# KEYBOARD.net
KiCad netlist of a schematic drawn in Altium Designer
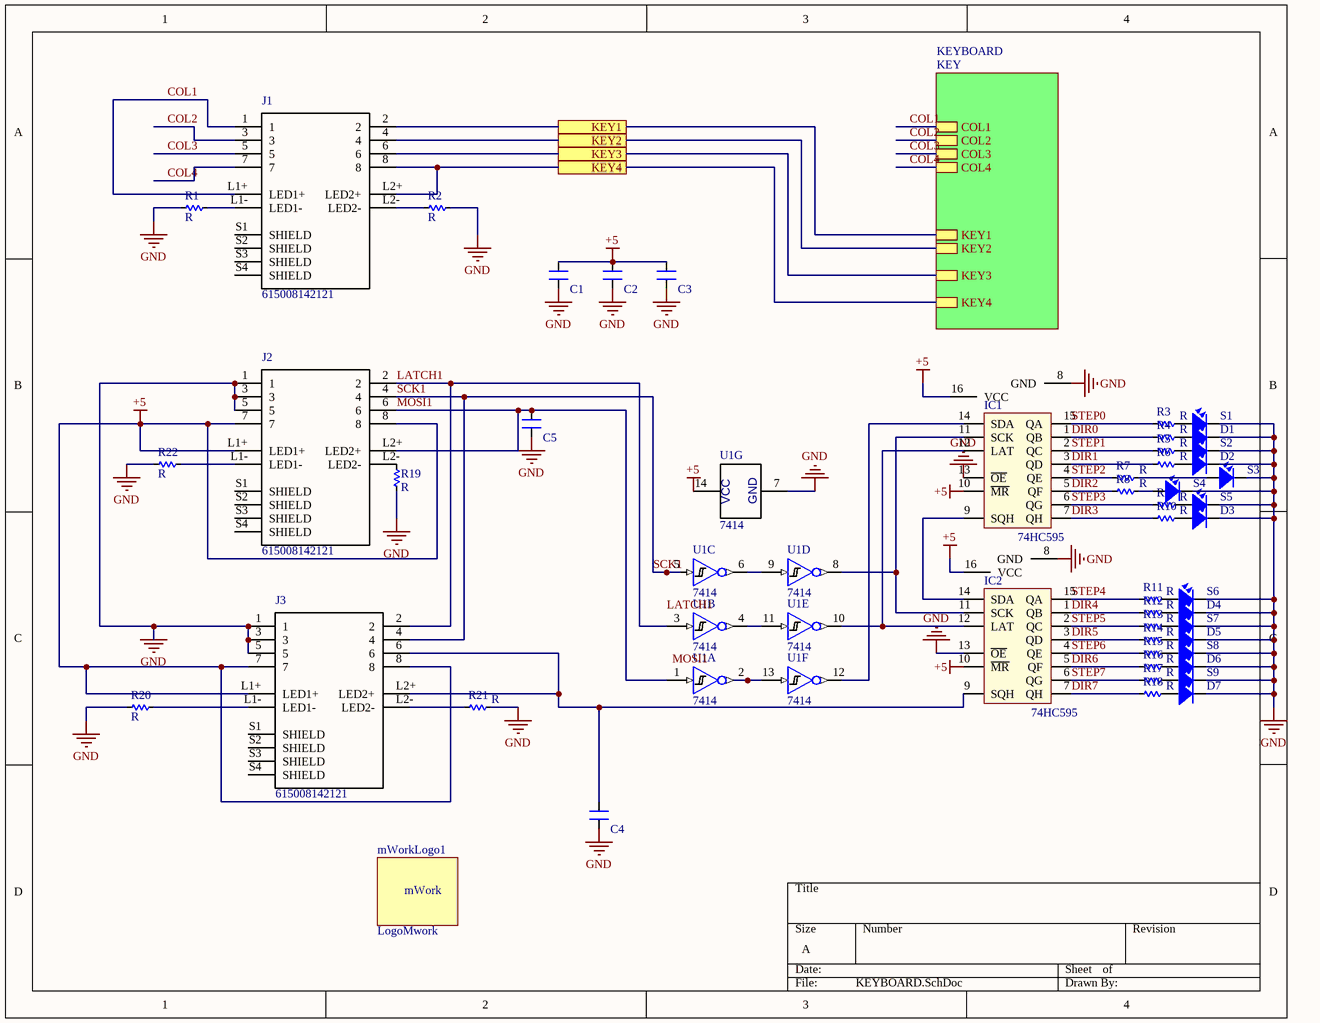
[diagram p0: KEYBOARD.SchDoc]

(export (version "E")
  (design (tool "Eeschema 10.0.6"))
  (components
    (comp (ref "C1") (value "CN") (footprint "CN-SMD-0603_big") (libsource (lib "nhan") (part "CN")))
    (comp (ref "C2") (value "CN") (footprint "CN-SMD-0603_big") (libsource (lib "nhan") (part "CN")))
    (comp (ref "C3") (value "CN") (footprint "CN-SMD-0603_big") (libsource (lib "nhan") (part "CN")))
    (comp (ref "C4") (value "CN") (footprint "CN-SMD-0603_big") (libsource (lib "nhan") (part "CN")))
    (comp (ref "C5") (value "CN") (footprint "CN-SMD-0603_big") (libsource (lib "nhan") (part "CN")))
    (comp (ref "D1") (value "LED") (footprint "LED-0805-Blue") (libsource (lib "LIBRARY") (part "LED SMD")))
    (comp (ref "D2") (value "LED") (footprint "LED-0805-Blue") (libsource (lib "LIBRARY") (part "LED SMD")))
    (comp (ref "D3") (value "LED") (footprint "LED-0805-Blue") (libsource (lib "LIBRARY") (part "LED SMD")))
    (comp (ref "D4") (value "LED") (footprint "LED-0805-Blue") (libsource (lib "LIBRARY") (part "LED SMD")))
    (comp (ref "D5") (value "LED") (footprint "LED-0805-Blue") (libsource (lib "LIBRARY") (part "LED SMD")))
    (comp (ref "D6") (value "LED") (footprint "LED-0805-Blue") (libsource (lib "LIBRARY") (part "LED SMD")))
    (comp (ref "D7") (value "LED") (footprint "LED-0805-Blue") (libsource (lib "LIBRARY") (part "LED SMD")))
    (comp (ref "IC1")
      (value "74HC595")
      (footprint "SO16")
      (description "8 Bit Serial input - Parallel Output")
      (libsource (lib "") (part "74595_1"))
    )
    (comp (ref "IC2")
      (value "74HC595")
      (footprint "SO16")
      (description "8 Bit Serial input - Parallel Output")
      (libsource (lib "BanLinhKien") (part "74595"))
    )
    (comp (ref "J1")
      (value "615008142121")
      (footprint "RJ45_8P8C")
      (description "Conn, Rj45 Jack, Shld, 1port, 8p8c, Cat5")
      (fields (field (name "MF") "WÃ¼rth Elektronik"))
      (libsource (lib "nhan") (part "RJ45_8P8C"))
    )
    (comp (ref "J2")
      (value "615008142121")
      (footprint "RJ45_8P8C")
      (description "Conn, Rj45 Jack, Shld, 1port, 8p8c, Cat5")
      (fields (field (name "MF") "WÃ¼rth Elektronik"))
      (libsource (lib "nhan") (part "RJ45_8P8C"))
    )
    (comp (ref "J3")
      (value "615008142121")
      (footprint "RJ45_8P8C")
      (description "Conn, Rj45 Jack, Shld, 1port, 8p8c, Cat5")
      (fields (field (name "MF") "WÃ¼rth Elektronik"))
      (libsource (lib "nhan") (part "RJ45_8P8C"))
    )
    (comp (ref "mWorkLogo1")
      (value "LogoMwork")
      (footprint "LogoMwork15*6")
      (libsource (lib "nhan") (part "LogoMwork"))
    )
    (comp (ref "R1") (value "R") (footprint "RES-SMD-0603_BIG") (libsource (lib "nhan") (part "R")))
    (comp (ref "R2") (value "R") (footprint "RES-SMD-0603_BIG") (libsource (lib "nhan") (part "R")))
    (comp (ref "R3") (value "R") (footprint "RES-SMD-0603_BIG") (libsource (lib "nhan") (part "R")))
    (comp (ref "R4") (value "R") (footprint "RES-SMD-0603_BIG") (libsource (lib "nhan") (part "R")))
    (comp (ref "R5") (value "R") (footprint "RES-SMD-0603_BIG") (libsource (lib "nhan") (part "R")))
    (comp (ref "R6") (value "R") (footprint "RES-SMD-0603_BIG") (libsource (lib "nhan") (part "R")))
    (comp (ref "R7") (value "R") (footprint "RES-SMD-0603_BIG") (libsource (lib "nhan") (part "R")))
    (comp (ref "R8") (value "R") (footprint "RES-SMD-0603_BIG") (libsource (lib "nhan") (part "R")))
    (comp (ref "R9") (value "R") (footprint "RES-SMD-0603_BIG") (libsource (lib "nhan") (part "R")))
    (comp (ref "R10") (value "R") (footprint "RES-SMD-0603_BIG") (libsource (lib "nhan") (part "R")))
    (comp (ref "R11") (value "R") (footprint "RES-SMD-0603_BIG") (libsource (lib "nhan") (part "R")))
    (comp (ref "R12") (value "R") (footprint "RES-SMD-0603_BIG") (libsource (lib "nhan") (part "R")))
    (comp (ref "R13") (value "R") (footprint "RES-SMD-0603_BIG") (libsource (lib "nhan") (part "R")))
    (comp (ref "R14") (value "R") (footprint "RES-SMD-0603_BIG") (libsource (lib "nhan") (part "R")))
    (comp (ref "R15") (value "R") (footprint "RES-SMD-0603_BIG") (libsource (lib "nhan") (part "R")))
    (comp (ref "R16") (value "R") (footprint "RES-SMD-0603_BIG") (libsource (lib "nhan") (part "R")))
    (comp (ref "R17") (value "R") (footprint "RES-SMD-0603_BIG") (libsource (lib "nhan") (part "R")))
    (comp (ref "R18") (value "R") (footprint "RES-SMD-0603_BIG") (libsource (lib "nhan") (part "R")))
    (comp (ref "R19") (value "R") (footprint "RES-SMD-0603_BIG") (libsource (lib "nhan") (part "R")))
    (comp (ref "R20") (value "R") (footprint "RES-SMD-0603_BIG") (libsource (lib "nhan") (part "R")))
    (comp (ref "R21") (value "R") (footprint "RES-SMD-0603_BIG") (libsource (lib "nhan") (part "R")))
    (comp (ref "R22") (value "R") (footprint "RES-SMD-0603_BIG") (libsource (lib "nhan") (part "R")))
    (comp (ref "S1") (value "LED") (footprint "LED-0805-Blue") (libsource (lib "LIBRARY") (part "LED SMD")))
    (comp (ref "S2") (value "LED") (footprint "LED-0805-Blue") (libsource (lib "LIBRARY") (part "LED SMD")))
    (comp (ref "S3") (value "LED") (footprint "LED-0805-Blue") (libsource (lib "LIBRARY") (part "LED SMD")))
    (comp (ref "S4") (value "LED") (footprint "LED-0805-Blue") (libsource (lib "LIBRARY") (part "LED SMD")))
    (comp (ref "S5") (value "LED") (footprint "LED-0805-Blue") (libsource (lib "LIBRARY") (part "LED SMD")))
    (comp (ref "S6") (value "LED") (footprint "LED-0805-Blue") (libsource (lib "LIBRARY") (part "LED SMD")))
    (comp (ref "S7") (value "LED") (footprint "LED-0805-Blue") (libsource (lib "LIBRARY") (part "LED SMD")))
    (comp (ref "S8") (value "LED") (footprint "LED-0805-Blue") (libsource (lib "LIBRARY") (part "LED SMD")))
    (comp (ref "S9") (value "LED") (footprint "LED-0805-Blue") (libsource (lib "LIBRARY") (part "LED SMD")))
    (comp (ref "U1")
      (value "7414")
      (footprint "SO14")
      (description "IC, M74HC04M, Hex Inverter, SO-14")
      (libsource (lib "BanLinhKien") (part "7414"))
    )
  )
  (nets
    (net (code "1") (name "+5") (class "Default")
      (node (ref "C1") (pin "2") (pinfunction "2_2") (pintype "passive"))
      (node (ref "C2") (pin "2") (pinfunction "2_2") (pintype "passive"))
      (node (ref "C3") (pin "2") (pinfunction "2_2") (pintype "passive"))
      (node (ref "IC1") (pin "10") (pinfunction "~{MR}_10") (pintype "passive"))
      (node (ref "IC1") (pin "16") (pinfunction "VCC_16") (pintype "passive"))
      (node (ref "IC2") (pin "10") (pinfunction "~{MR}_10") (pintype "passive"))
      (node (ref "IC2") (pin "16") (pinfunction "VCC_16") (pintype "passive"))
      (node (ref "J2") (pin "7") (pinfunction "7_7") (pintype "passive"))
      (node (ref "J2") (pin "8") (pinfunction "8_8") (pintype "passive"))
      (node (ref "J2") (pin "L1+") (pinfunction "LED1+_L1+") (pintype "passive"))
      (node (ref "J3") (pin "7") (pinfunction "7_7") (pintype "passive"))
      (node (ref "J3") (pin "8") (pinfunction "8_8") (pintype "passive"))
      (node (ref "J3") (pin "L1+") (pinfunction "LED1+_L1+") (pintype "passive"))
      (node (ref "U1") (pin "14") (pinfunction "VCC_14") (pintype "passive"))
    )
    (net (code "2") (name "/COL1") (class "Default")
      (node (ref "J1") (pin "1") (pinfunction "1_1") (pintype "passive"))
      (node (ref "J1") (pin "L1+") (pinfunction "LED1+_L1+") (pintype "passive"))
    )
    (net (code "3") (name "/COL2") (class "Default")
      (node (ref "J1") (pin "3") (pinfunction "3_3") (pintype "passive"))
    )
    (net (code "4") (name "/COL3") (class "Default")
      (node (ref "J1") (pin "5") (pinfunction "5_5") (pintype "passive"))
    )
    (net (code "5") (name "/COL4") (class "Default")
      (node (ref "J1") (pin "7") (pinfunction "7_7") (pintype "passive"))
    )
    (net (code "6") (name "/DIR0") (class "Default")
      (node (ref "IC1") (pin "1") (pinfunction "QB_1") (pintype "passive"))
      (node (ref "R4") (pin "1") (pinfunction "1_1") (pintype "passive"))
    )
    (net (code "7") (name "/DIR1") (class "Default")
      (node (ref "IC1") (pin "3") (pinfunction "QD_3") (pintype "passive"))
      (node (ref "R6") (pin "1") (pinfunction "1_1") (pintype "passive"))
    )
    (net (code "8") (name "/DIR2") (class "Default")
      (node (ref "IC1") (pin "5") (pinfunction "QF_5") (pintype "passive"))
      (node (ref "R8") (pin "1") (pinfunction "1_1") (pintype "passive"))
    )
    (net (code "9") (name "/DIR3") (class "Default")
      (node (ref "IC1") (pin "7") (pinfunction "QH_7") (pintype "passive"))
      (node (ref "R10") (pin "1") (pinfunction "1_1") (pintype "passive"))
    )
    (net (code "10") (name "/DIR4") (class "Default")
      (node (ref "IC2") (pin "1") (pinfunction "QB_1") (pintype "passive"))
      (node (ref "R12") (pin "1") (pinfunction "1_1") (pintype "passive"))
    )
    (net (code "11") (name "/DIR5") (class "Default")
      (node (ref "IC2") (pin "3") (pinfunction "QD_3") (pintype "passive"))
      (node (ref "R14") (pin "1") (pinfunction "1_1") (pintype "passive"))
    )
    (net (code "12") (name "/DIR6") (class "Default")
      (node (ref "IC2") (pin "5") (pinfunction "QF_5") (pintype "passive"))
      (node (ref "R16") (pin "1") (pinfunction "1_1") (pintype "passive"))
    )
    (net (code "13") (name "/DIR7") (class "Default")
      (node (ref "IC2") (pin "7") (pinfunction "QH_7") (pintype "passive"))
      (node (ref "R18") (pin "1") (pinfunction "1_1") (pintype "passive"))
    )
    (net (code "14") (name "/KEY1") (class "Default")
      (node (ref "J1") (pin "2") (pinfunction "2_2") (pintype "passive"))
    )
    (net (code "15") (name "/KEY2") (class "Default")
      (node (ref "J1") (pin "4") (pinfunction "4_4") (pintype "passive"))
    )
    (net (code "16") (name "/KEY3") (class "Default")
      (node (ref "J1") (pin "6") (pinfunction "6_6") (pintype "passive"))
    )
    (net (code "17") (name "/KEY4") (class "Default")
      (node (ref "J1") (pin "8") (pinfunction "8_8") (pintype "passive"))
      (node (ref "J1") (pin "L2+") (pinfunction "LED2+_L2+") (pintype "passive"))
    )
    (net (code "18") (name "/LATCH1") (class "Default")
      (node (ref "J2") (pin "2") (pinfunction "2_2") (pintype "passive"))
      (node (ref "J3") (pin "2") (pinfunction "2_2") (pintype "passive"))
      (node (ref "U1") (pin "3") (pinfunction "A_3") (pintype "input"))
    )
    (net (code "19") (name "/MOSI1") (class "Default")
      (node (ref "C5") (pin "2") (pinfunction "2_2") (pintype "passive"))
      (node (ref "J2") (pin "6") (pinfunction "6_6") (pintype "passive"))
      (node (ref "J2") (pin "L2+") (pinfunction "LED2+_L2+") (pintype "passive"))
      (node (ref "U1") (pin "1") (pinfunction "A_1") (pintype "input"))
    )
    (net (code "20") (name "/SCK1") (class "Default")
      (node (ref "J2") (pin "4") (pinfunction "4_4") (pintype "passive"))
      (node (ref "J3") (pin "4") (pinfunction "4_4") (pintype "passive"))
      (node (ref "U1") (pin "5") (pinfunction "A_5") (pintype "input"))
    )
    (net (code "21") (name "/STEP0") (class "Default")
      (node (ref "IC1") (pin "15") (pinfunction "QA_15") (pintype "passive"))
      (node (ref "R3") (pin "1") (pinfunction "1_1") (pintype "passive"))
    )
    (net (code "22") (name "/STEP1") (class "Default")
      (node (ref "IC1") (pin "2") (pinfunction "QC_2") (pintype "passive"))
      (node (ref "R5") (pin "1") (pinfunction "1_1") (pintype "passive"))
    )
    (net (code "23") (name "/STEP2") (class "Default")
      (node (ref "IC1") (pin "4") (pinfunction "QE_4") (pintype "passive"))
      (node (ref "R7") (pin "1") (pinfunction "1_1") (pintype "passive"))
    )
    (net (code "24") (name "/STEP3") (class "Default")
      (node (ref "IC1") (pin "6") (pinfunction "QG_6") (pintype "passive"))
      (node (ref "R9") (pin "1") (pinfunction "1_1") (pintype "passive"))
    )
    (net (code "25") (name "/STEP4") (class "Default")
      (node (ref "IC2") (pin "15") (pinfunction "QA_15") (pintype "passive"))
      (node (ref "R11") (pin "1") (pinfunction "1_1") (pintype "passive"))
    )
    (net (code "26") (name "/STEP5") (class "Default")
      (node (ref "IC2") (pin "2") (pinfunction "QC_2") (pintype "passive"))
      (node (ref "R13") (pin "1") (pinfunction "1_1") (pintype "passive"))
    )
    (net (code "27") (name "/STEP6") (class "Default")
      (node (ref "IC2") (pin "4") (pinfunction "QE_4") (pintype "passive"))
      (node (ref "R15") (pin "1") (pinfunction "1_1") (pintype "passive"))
    )
    (net (code "28") (name "/STEP7") (class "Default")
      (node (ref "IC2") (pin "6") (pinfunction "QG_6") (pintype "passive"))
      (node (ref "R17") (pin "1") (pinfunction "1_1") (pintype "passive"))
    )
    (net (code "29") (name "GND") (class "Default")
      (node (ref "C1") (pin "1") (pinfunction "1_1") (pintype "passive"))
      (node (ref "C2") (pin "1") (pinfunction "1_1") (pintype "passive"))
      (node (ref "C3") (pin "1") (pinfunction "1_1") (pintype "passive"))
      (node (ref "C4") (pin "1") (pinfunction "1_1") (pintype "passive"))
      (node (ref "C5") (pin "1") (pinfunction "1_1") (pintype "passive"))
      (node (ref "D1") (pin "2") (pinfunction "2_2") (pintype "passive"))
      (node (ref "D2") (pin "2") (pinfunction "2_2") (pintype "passive"))
      (node (ref "D3") (pin "2") (pinfunction "2_2") (pintype "passive"))
      (node (ref "D4") (pin "2") (pinfunction "2_2") (pintype "passive"))
      (node (ref "D5") (pin "2") (pinfunction "2_2") (pintype "passive"))
      (node (ref "D6") (pin "2") (pinfunction "2_2") (pintype "passive"))
      (node (ref "D7") (pin "2") (pinfunction "2_2") (pintype "passive"))
      (node (ref "IC1") (pin "13") (pinfunction "~{OE}_13") (pintype "passive"))
      (node (ref "IC1") (pin "8") (pinfunction "GND_8") (pintype "passive"))
      (node (ref "IC2") (pin "13") (pinfunction "~{OE}_13") (pintype "passive"))
      (node (ref "IC2") (pin "8") (pinfunction "GND_8") (pintype "passive"))
      (node (ref "J2") (pin "1") (pinfunction "1_1") (pintype "passive"))
      (node (ref "J2") (pin "3") (pinfunction "3_3") (pintype "passive"))
      (node (ref "J2") (pin "5") (pinfunction "5_5") (pintype "passive"))
      (node (ref "J3") (pin "1") (pinfunction "1_1") (pintype "passive"))
      (node (ref "J3") (pin "3") (pinfunction "3_3") (pintype "passive"))
      (node (ref "J3") (pin "5") (pinfunction "5_5") (pintype "passive"))
      (node (ref "R1") (pin "2") (pinfunction "2_2") (pintype "passive"))
      (node (ref "R19") (pin "1") (pinfunction "1_1") (pintype "passive"))
      (node (ref "R2") (pin "1") (pinfunction "1_1") (pintype "passive"))
      (node (ref "R20") (pin "2") (pinfunction "2_2") (pintype "passive"))
      (node (ref "R21") (pin "2") (pinfunction "2_2") (pintype "passive"))
      (node (ref "R22") (pin "2") (pinfunction "2_2") (pintype "passive"))
      (node (ref "S1") (pin "2") (pinfunction "2_2") (pintype "passive"))
      (node (ref "S2") (pin "2") (pinfunction "2_2") (pintype "passive"))
      (node (ref "S3") (pin "2") (pinfunction "2_2") (pintype "passive"))
      (node (ref "S4") (pin "2") (pinfunction "2_2") (pintype "passive"))
      (node (ref "S5") (pin "2") (pinfunction "2_2") (pintype "passive"))
      (node (ref "S6") (pin "2") (pinfunction "2_2") (pintype "passive"))
      (node (ref "S7") (pin "2") (pinfunction "2_2") (pintype "passive"))
      (node (ref "S8") (pin "2") (pinfunction "2_2") (pintype "passive"))
      (node (ref "S9") (pin "2") (pinfunction "2_2") (pintype "passive"))
      (node (ref "U1") (pin "7") (pinfunction "GND_7") (pintype "passive"))
    )
    (net (code "30") (name "Net-(D1-Pad1)") (class "Default")
      (node (ref "D1") (pin "1") (pinfunction "1_1") (pintype "passive"))
      (node (ref "R4") (pin "2") (pinfunction "2_2") (pintype "passive"))
    )
    (net (code "31") (name "Net-(D2-Pad1)") (class "Default")
      (node (ref "D2") (pin "1") (pinfunction "1_1") (pintype "passive"))
      (node (ref "R6") (pin "2") (pinfunction "2_2") (pintype "passive"))
    )
    (net (code "32") (name "Net-(D3-Pad1)") (class "Default")
      (node (ref "D3") (pin "1") (pinfunction "1_1") (pintype "passive"))
      (node (ref "R10") (pin "2") (pinfunction "2_2") (pintype "passive"))
    )
    (net (code "33") (name "Net-(D4-Pad1)") (class "Default")
      (node (ref "D4") (pin "1") (pinfunction "1_1") (pintype "passive"))
      (node (ref "R12") (pin "2") (pinfunction "2_2") (pintype "passive"))
    )
    (net (code "34") (name "Net-(D5-Pad1)") (class "Default")
      (node (ref "D5") (pin "1") (pinfunction "1_1") (pintype "passive"))
      (node (ref "R14") (pin "2") (pinfunction "2_2") (pintype "passive"))
    )
    (net (code "35") (name "Net-(D6-Pad1)") (class "Default")
      (node (ref "D6") (pin "1") (pinfunction "1_1") (pintype "passive"))
      (node (ref "R16") (pin "2") (pinfunction "2_2") (pintype "passive"))
    )
    (net (code "36") (name "Net-(D7-Pad1)") (class "Default")
      (node (ref "D7") (pin "1") (pinfunction "1_1") (pintype "passive"))
      (node (ref "R18") (pin "2") (pinfunction "2_2") (pintype "passive"))
    )
    (net (code "37") (name "Net-(IC1-LAT)") (class "Default")
      (node (ref "IC1") (pin "12") (pinfunction "LAT_12") (pintype "passive"))
      (node (ref "IC2") (pin "12") (pinfunction "LAT_12") (pintype "passive"))
      (node (ref "U1") (pin "10") (pinfunction "Y_10") (pintype "output"))
    )
    (net (code "38") (name "Net-(IC1-SCK)") (class "Default")
      (node (ref "IC1") (pin "11") (pinfunction "SCK_11") (pintype "passive"))
      (node (ref "IC2") (pin "11") (pinfunction "SCK_11") (pintype "passive"))
      (node (ref "U1") (pin "8") (pinfunction "Y_8") (pintype "output"))
    )
    (net (code "39") (name "Net-(IC1-SDA)") (class "Default")
      (node (ref "IC1") (pin "14") (pinfunction "SDA_14") (pintype "passive"))
      (node (ref "U1") (pin "12") (pinfunction "Y_12") (pintype "output"))
    )
    (net (code "40") (name "Net-(IC1-SQH)") (class "Default")
      (node (ref "IC1") (pin "9") (pinfunction "SQH_9") (pintype "passive"))
      (node (ref "IC2") (pin "14") (pinfunction "SDA_14") (pintype "passive"))
    )
    (net (code "41") (name "Net-(IC2-SQH)") (class "Default")
      (node (ref "C4") (pin "2") (pinfunction "2_2") (pintype "passive"))
      (node (ref "IC2") (pin "9") (pinfunction "SQH_9") (pintype "passive"))
      (node (ref "J3") (pin "6") (pinfunction "6_6") (pintype "passive"))
      (node (ref "J3") (pin "L2+") (pinfunction "LED2+_L2+") (pintype "passive"))
    )
    (net (code "42") (name "Net-(J1-LED1-)") (class "Default")
      (node (ref "J1") (pin "L1-") (pinfunction "LED1-_L1-") (pintype "passive"))
      (node (ref "R1") (pin "1") (pinfunction "1_1") (pintype "passive"))
    )
    (net (code "43") (name "Net-(J1-LED2-)") (class "Default")
      (node (ref "J1") (pin "L2-") (pinfunction "LED2-_L2-") (pintype "passive"))
      (node (ref "R2") (pin "2") (pinfunction "2_2") (pintype "passive"))
    )
    (net (code "44") (name "Net-(J2-LED1-)") (class "Default")
      (node (ref "J2") (pin "L1-") (pinfunction "LED1-_L1-") (pintype "passive"))
      (node (ref "R22") (pin "1") (pinfunction "1_1") (pintype "passive"))
    )
    (net (code "45") (name "Net-(J2-LED2-)") (class "Default")
      (node (ref "J2") (pin "L2-") (pinfunction "LED2-_L2-") (pintype "passive"))
      (node (ref "R19") (pin "2") (pinfunction "2_2") (pintype "passive"))
    )
    (net (code "46") (name "Net-(J3-LED1-)") (class "Default")
      (node (ref "J3") (pin "L1-") (pinfunction "LED1-_L1-") (pintype "passive"))
      (node (ref "R20") (pin "1") (pinfunction "1_1") (pintype "passive"))
    )
    (net (code "47") (name "Net-(J3-LED2-)") (class "Default")
      (node (ref "J3") (pin "L2-") (pinfunction "LED2-_L2-") (pintype "passive"))
      (node (ref "R21") (pin "1") (pinfunction "1_1") (pintype "passive"))
    )
    (net (code "48") (name "Net-(R3-Pad2)") (class "Default")
      (node (ref "R3") (pin "2") (pinfunction "2_2") (pintype "passive"))
      (node (ref "S1") (pin "1") (pinfunction "1_1") (pintype "passive"))
    )
    (net (code "49") (name "Net-(R5-Pad2)") (class "Default")
      (node (ref "R5") (pin "2") (pinfunction "2_2") (pintype "passive"))
      (node (ref "S2") (pin "1") (pinfunction "1_1") (pintype "passive"))
    )
    (net (code "50") (name "Net-(R7-Pad2)") (class "Default")
      (node (ref "R7") (pin "2") (pinfunction "2_2") (pintype "passive"))
      (node (ref "S3") (pin "1") (pinfunction "1_1") (pintype "passive"))
    )
    (net (code "51") (name "Net-(R8-Pad2)") (class "Default")
      (node (ref "R8") (pin "2") (pinfunction "2_2") (pintype "passive"))
      (node (ref "S4") (pin "1") (pinfunction "1_1") (pintype "passive"))
    )
    (net (code "52") (name "Net-(R9-Pad2)") (class "Default")
      (node (ref "R9") (pin "2") (pinfunction "2_2") (pintype "passive"))
      (node (ref "S5") (pin "1") (pinfunction "1_1") (pintype "passive"))
    )
    (net (code "53") (name "Net-(R11-Pad2)") (class "Default")
      (node (ref "R11") (pin "2") (pinfunction "2_2") (pintype "passive"))
      (node (ref "S6") (pin "1") (pinfunction "1_1") (pintype "passive"))
    )
    (net (code "54") (name "Net-(R13-Pad2)") (class "Default")
      (node (ref "R13") (pin "2") (pinfunction "2_2") (pintype "passive"))
      (node (ref "S7") (pin "1") (pinfunction "1_1") (pintype "passive"))
    )
    (net (code "55") (name "Net-(R15-Pad2)") (class "Default")
      (node (ref "R15") (pin "2") (pinfunction "2_2") (pintype "passive"))
      (node (ref "S8") (pin "1") (pinfunction "1_1") (pintype "passive"))
    )
    (net (code "56") (name "Net-(R17-Pad2)") (class "Default")
      (node (ref "R17") (pin "2") (pinfunction "2_2") (pintype "passive"))
      (node (ref "S9") (pin "1") (pinfunction "1_1") (pintype "passive"))
    )
    (net (code "57") (name "Net-(U1A-Y)") (class "Default")
      (node (ref "U1") (pin "13") (pinfunction "A_13") (pintype "input"))
      (node (ref "U1") (pin "2") (pinfunction "Y_2") (pintype "output"))
    )
    (net (code "58") (name "Net-(U1B-Y)") (class "Default")
      (node (ref "U1") (pin "11") (pinfunction "A_11") (pintype "input"))
      (node (ref "U1") (pin "4") (pinfunction "Y_4") (pintype "output"))
    )
    (net (code "59") (name "Net-(U1C-Y)") (class "Default")
      (node (ref "U1") (pin "6") (pinfunction "Y_6") (pintype "output"))
      (node (ref "U1") (pin "9") (pinfunction "A_9") (pintype "input"))
    )
    (net (code "60") (name "unconnected-(J1-SHIELD-PadS1)") (class "Default")
      (node (ref "J1") (pin "S1") (pinfunction "SHIELD_S1") (pintype "passive"))
    )
    (net (code "61") (name "unconnected-(J1-SHIELD-PadS2)") (class "Default")
      (node (ref "J1") (pin "S2") (pinfunction "SHIELD_S2") (pintype "passive"))
    )
    (net (code "62") (name "unconnected-(J1-SHIELD-PadS3)") (class "Default")
      (node (ref "J1") (pin "S3") (pinfunction "SHIELD_S3") (pintype "passive"))
    )
    (net (code "63") (name "unconnected-(J1-SHIELD-PadS4)") (class "Default")
      (node (ref "J1") (pin "S4") (pinfunction "SHIELD_S4") (pintype "passive"))
    )
    (net (code "64") (name "unconnected-(J2-SHIELD-PadS1)") (class "Default")
      (node (ref "J2") (pin "S1") (pinfunction "SHIELD_S1") (pintype "passive"))
    )
    (net (code "65") (name "unconnected-(J2-SHIELD-PadS2)") (class "Default")
      (node (ref "J2") (pin "S2") (pinfunction "SHIELD_S2") (pintype "passive"))
    )
    (net (code "66") (name "unconnected-(J2-SHIELD-PadS3)") (class "Default")
      (node (ref "J2") (pin "S3") (pinfunction "SHIELD_S3") (pintype "passive"))
    )
    (net (code "67") (name "unconnected-(J2-SHIELD-PadS4)") (class "Default")
      (node (ref "J2") (pin "S4") (pinfunction "SHIELD_S4") (pintype "passive"))
    )
    (net (code "68") (name "unconnected-(J3-SHIELD-PadS1)") (class "Default")
      (node (ref "J3") (pin "S1") (pinfunction "SHIELD_S1") (pintype "passive"))
    )
    (net (code "69") (name "unconnected-(J3-SHIELD-PadS2)") (class "Default")
      (node (ref "J3") (pin "S2") (pinfunction "SHIELD_S2") (pintype "passive"))
    )
    (net (code "70") (name "unconnected-(J3-SHIELD-PadS3)") (class "Default")
      (node (ref "J3") (pin "S3") (pinfunction "SHIELD_S3") (pintype "passive"))
    )
    (net (code "71") (name "unconnected-(J3-SHIELD-PadS4)") (class "Default")
      (node (ref "J3") (pin "S4") (pinfunction "SHIELD_S4") (pintype "passive"))
    )
  )
)
